# ADJ5V3_3V12V_Sheet_2021-07-20.net
KiCad netlist of a schematic drawn in Altium Designer
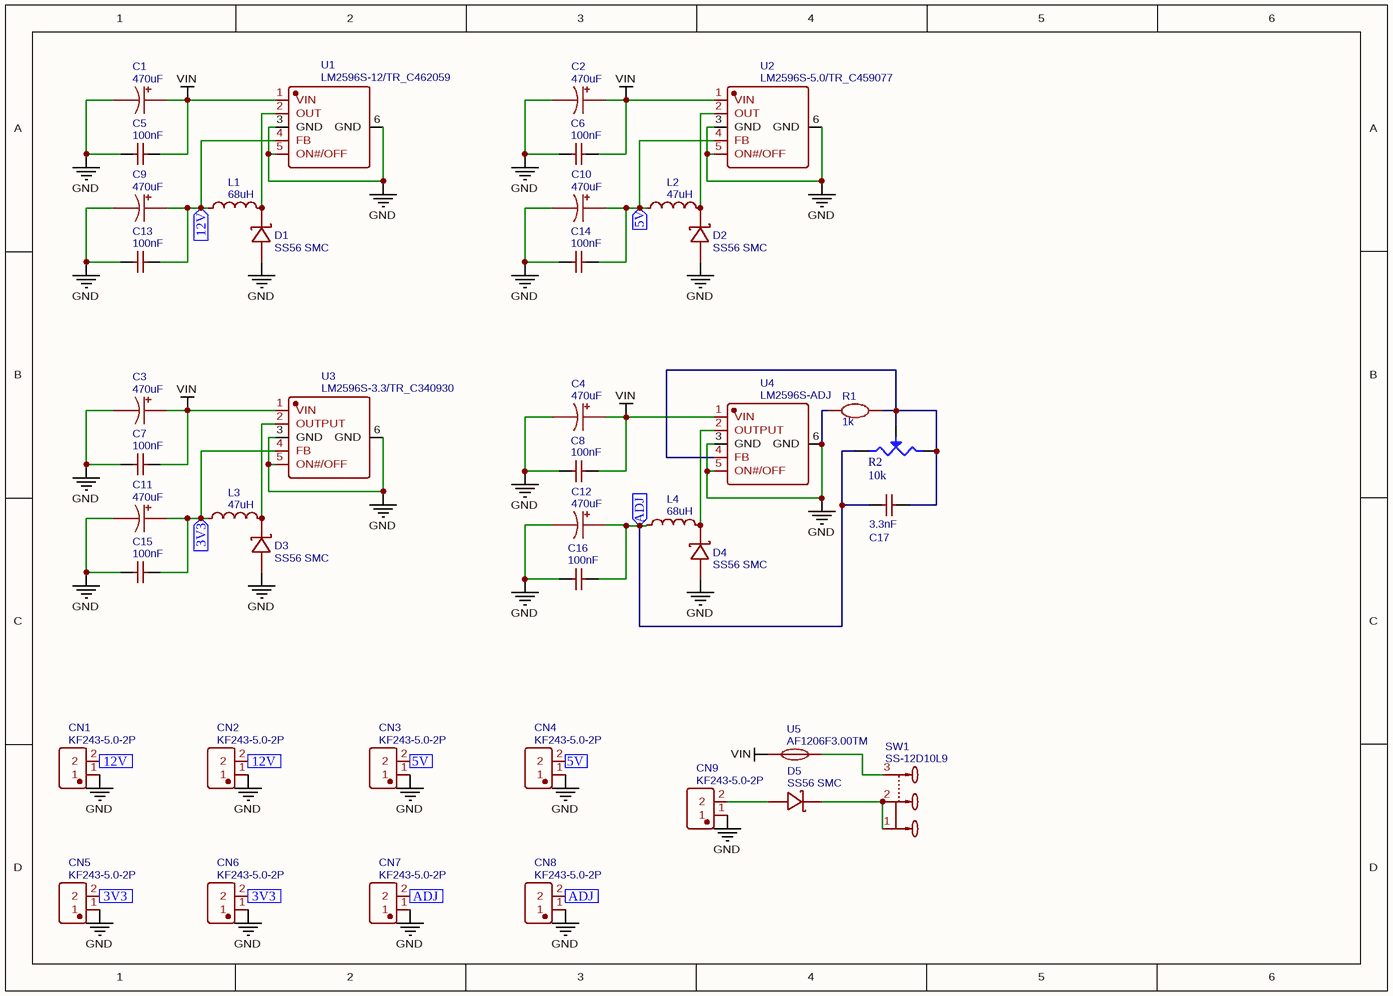
[diagram p0: ADJ5V3.3V12V_Sheet_2021-07-20.schdoc]

(export (version "E")
  (design (tool "Eeschema 10.0.6"))
  (components
    (comp (ref "C1")
      (value "470uF")
      (footprint "CAP-SMD_BD12.5-L13.0-W13.0-FD")
      (fields
        (field (name "BOM_MANUFACTURER PART") "VEJ471M1HTR-1316")
        (field (name "BOM_SUPPLIER PART") "C108926")
        (field (name "CONTRIBUTOR") "LCSC")
      )
      (libsource (lib "altium-import") (part "root_3_470uF_"))
    )
    (comp (ref "C2")
      (value "470uF")
      (footprint "CAP-SMD_BD12.5-L13.0-W13.0-FD")
      (fields
        (field (name "BOM_MANUFACTURER PART") "VEJ471M1HTR-1316")
        (field (name "BOM_SUPPLIER PART") "C108926")
        (field (name "CONTRIBUTOR") "LCSC")
      )
      (libsource (lib "altium-import") (part "root_3_470uF_"))
    )
    (comp (ref "C3")
      (value "470uF")
      (footprint "CAP-SMD_BD12.5-L13.0-W13.0-FD")
      (fields
        (field (name "BOM_MANUFACTURER PART") "VEJ471M1HTR-1316")
        (field (name "BOM_SUPPLIER PART") "C108926")
        (field (name "CONTRIBUTOR") "LCSC")
      )
      (libsource (lib "altium-import") (part "root_3_470uF_"))
    )
    (comp (ref "C4")
      (value "470uF")
      (footprint "CAP-SMD_BD12.5-L13.0-W13.0-FD")
      (fields
        (field (name "BOM_MANUFACTURER PART") "VEJ471M1HTR-1316")
        (field (name "BOM_SUPPLIER PART") "C108926")
        (field (name "CONTRIBUTOR") "LCSC")
      )
      (libsource (lib "altium-import") (part "root_3_470uF_"))
    )
    (comp (ref "C5")
      (value "100nF")
      (footprint "C1210")
      (fields
        (field (name "BOM_MANUFACTURER PART") "C1210X104K251T")
        (field (name "BOM_SUPPLIER PART") "C106103")
      )
      (libsource (lib "altium-import") (part "root_0_100nF_"))
    )
    (comp (ref "C6")
      (value "100nF")
      (footprint "C1210")
      (fields
        (field (name "BOM_MANUFACTURER PART") "C1210X104K251T")
        (field (name "BOM_SUPPLIER PART") "C106103")
      )
      (libsource (lib "altium-import") (part "root_0_100nF_"))
    )
    (comp (ref "C7")
      (value "100nF")
      (footprint "C1210")
      (fields
        (field (name "BOM_MANUFACTURER PART") "C1210X104K251T")
        (field (name "BOM_SUPPLIER PART") "C106103")
      )
      (libsource (lib "altium-import") (part "root_0_100nF_"))
    )
    (comp (ref "C8")
      (value "100nF")
      (footprint "C1210")
      (fields
        (field (name "BOM_MANUFACTURER PART") "C1210X104K251T")
        (field (name "BOM_SUPPLIER PART") "C106103")
      )
      (libsource (lib "altium-import") (part "root_0_100nF_"))
    )
    (comp (ref "C9")
      (value "470uF")
      (footprint "CAP-SMD_BD12.5-L13.0-W13.0-FD")
      (fields
        (field (name "BOM_MANUFACTURER PART") "VEJ471M1HTR-1316")
        (field (name "BOM_SUPPLIER PART") "C108926")
        (field (name "CONTRIBUTOR") "LCSC")
      )
      (libsource (lib "altium-import") (part "root_3_470uF_"))
    )
    (comp (ref "C10")
      (value "470uF")
      (footprint "CAP-SMD_BD12.5-L13.0-W13.0-FD")
      (fields
        (field (name "BOM_MANUFACTURER PART") "VEJ471M1HTR-1316")
        (field (name "BOM_SUPPLIER PART") "C108926")
        (field (name "CONTRIBUTOR") "LCSC")
      )
      (libsource (lib "altium-import") (part "root_3_470uF_"))
    )
    (comp (ref "C11")
      (value "470uF")
      (footprint "CAP-SMD_BD12.5-L13.0-W13.0-FD")
      (fields
        (field (name "BOM_MANUFACTURER PART") "VEJ471M1HTR-1316")
        (field (name "BOM_SUPPLIER PART") "C108926")
        (field (name "CONTRIBUTOR") "LCSC")
      )
      (libsource (lib "altium-import") (part "root_3_470uF_"))
    )
    (comp (ref "C12")
      (value "470uF")
      (footprint "CAP-SMD_BD12.5-L13.0-W13.0-FD")
      (fields
        (field (name "BOM_MANUFACTURER PART") "VEJ471M1HTR-1316")
        (field (name "BOM_SUPPLIER PART") "C108926")
        (field (name "CONTRIBUTOR") "LCSC")
      )
      (libsource (lib "altium-import") (part "root_3_470uF_"))
    )
    (comp (ref "C13")
      (value "100nF")
      (footprint "C1210")
      (fields
        (field (name "BOM_MANUFACTURER PART") "C1210X104K251T")
        (field (name "BOM_SUPPLIER PART") "C106103")
      )
      (libsource (lib "altium-import") (part "root_0_100nF_"))
    )
    (comp (ref "C14")
      (value "100nF")
      (footprint "C1210")
      (fields
        (field (name "BOM_MANUFACTURER PART") "C1210X104K251T")
        (field (name "BOM_SUPPLIER PART") "C106103")
      )
      (libsource (lib "altium-import") (part "root_0_100nF_"))
    )
    (comp (ref "C15")
      (value "100nF")
      (footprint "C1210")
      (fields
        (field (name "BOM_MANUFACTURER PART") "C1210X104K251T")
        (field (name "BOM_SUPPLIER PART") "C106103")
      )
      (libsource (lib "altium-import") (part "root_0_100nF_"))
    )
    (comp (ref "C16")
      (value "100nF")
      (footprint "C1210")
      (fields
        (field (name "BOM_MANUFACTURER PART") "C1210X104K251T")
        (field (name "BOM_SUPPLIER PART") "C106103")
      )
      (libsource (lib "altium-import") (part "root_0_100nF_"))
    )
    (comp (ref "C17")
      (value "3.3nF")
      (footprint "C1210")
      (fields
        (field (name "BOM_MANUFACTURER PART") "C1210X104K251T")
        (field (name "BOM_SUPPLIER PART") "C106103")
      )
      (libsource (lib "altium-import") (part "root_0_100nF_"))
    )
    (comp (ref "CN1")
      (value "KF243-5.0-2P")
      (footprint "CONN-TH_P5.00_KF243-5.0-2P")
      (fields (field (name "BOM_SUPPLIER PART") "C475222") (field (name "CONTRIBUTOR") "LCSC"))
      (libsource (lib "altium-import") (part "root_2_KF243-5.0-2P_"))
    )
    (comp (ref "CN2")
      (value "KF243-5.0-2P")
      (footprint "CONN-TH_P5.00_KF243-5.0-2P")
      (fields (field (name "BOM_SUPPLIER PART") "C475222") (field (name "CONTRIBUTOR") "LCSC"))
      (libsource (lib "altium-import") (part "root_2_KF243-5.0-2P_"))
    )
    (comp (ref "CN3")
      (value "KF243-5.0-2P")
      (footprint "CONN-TH_P5.00_KF243-5.0-2P")
      (fields (field (name "BOM_SUPPLIER PART") "C475222") (field (name "CONTRIBUTOR") "LCSC"))
      (libsource (lib "altium-import") (part "root_2_KF243-5.0-2P_"))
    )
    (comp (ref "CN4")
      (value "KF243-5.0-2P")
      (footprint "CONN-TH_P5.00_KF243-5.0-2P")
      (fields (field (name "BOM_SUPPLIER PART") "C475222") (field (name "CONTRIBUTOR") "LCSC"))
      (libsource (lib "altium-import") (part "root_2_KF243-5.0-2P_"))
    )
    (comp (ref "CN5")
      (value "KF243-5.0-2P")
      (footprint "CONN-TH_P5.00_KF243-5.0-2P")
      (fields (field (name "BOM_SUPPLIER PART") "C475222") (field (name "CONTRIBUTOR") "LCSC"))
      (libsource (lib "altium-import") (part "root_2_KF243-5.0-2P_"))
    )
    (comp (ref "CN6")
      (value "KF243-5.0-2P")
      (footprint "CONN-TH_P5.00_KF243-5.0-2P")
      (fields (field (name "BOM_SUPPLIER PART") "C475222") (field (name "CONTRIBUTOR") "LCSC"))
      (libsource (lib "altium-import") (part "root_2_KF243-5.0-2P_"))
    )
    (comp (ref "CN7")
      (value "KF243-5.0-2P")
      (footprint "CONN-TH_P5.00_KF243-5.0-2P")
      (fields (field (name "BOM_SUPPLIER PART") "C475222") (field (name "CONTRIBUTOR") "LCSC"))
      (libsource (lib "altium-import") (part "root_2_KF243-5.0-2P_"))
    )
    (comp (ref "CN8")
      (value "KF243-5.0-2P")
      (footprint "CONN-TH_P5.00_KF243-5.0-2P")
      (fields (field (name "BOM_SUPPLIER PART") "C475222") (field (name "CONTRIBUTOR") "LCSC"))
      (libsource (lib "altium-import") (part "root_2_KF243-5.0-2P_"))
    )
    (comp (ref "CN9")
      (value "KF243-5.0-2P")
      (footprint "CONN-TH_P5.00_KF243-5.0-2P")
      (fields (field (name "BOM_SUPPLIER PART") "C475222") (field (name "CONTRIBUTOR") "LCSC"))
      (libsource (lib "altium-import") (part "root_2_KF243-5.0-2P_"))
    )
    (comp (ref "D1")
      (value "SS56 SMC")
      (footprint "SMC_L7.1-W6.2-LS8.1-FD")
      (fields (field (name "BOM_SUPPLIER PART") "C24138"))
      (libsource (lib "altium-import") (part "root_1_SS56 SMC_"))
    )
    (comp (ref "D2")
      (value "SS56 SMC")
      (footprint "SMC_L7.1-W6.2-LS8.1-FD")
      (fields (field (name "BOM_SUPPLIER PART") "C24138"))
      (libsource (lib "altium-import") (part "root_1_SS56 SMC_"))
    )
    (comp (ref "D3")
      (value "SS56 SMC")
      (footprint "SMC_L7.1-W6.2-LS8.1-FD")
      (fields (field (name "BOM_SUPPLIER PART") "C24138"))
      (libsource (lib "altium-import") (part "root_1_SS56 SMC_"))
    )
    (comp (ref "D4")
      (value "SS56 SMC")
      (footprint "SMC_L7.1-W6.2-LS8.1-FD")
      (fields (field (name "BOM_SUPPLIER PART") "C24138"))
      (libsource (lib "altium-import") (part "root_1_SS56 SMC_"))
    )
    (comp (ref "D5")
      (value "SS56 SMC")
      (footprint "SMC_L7.1-W6.2-LS8.1-FD")
      (fields (field (name "BOM_SUPPLIER PART") "C24138"))
      (libsource (lib "altium-import") (part "root_0_SS56 SMC_"))
    )
    (comp (ref "L1")
      (value "68uH")
      (footprint "IND-SMD_L11.5-W10.0")
      (fields (field (name "BOM_SUPPLIER PART") "C497902") (field (name "CONTRIBUTOR") "LCSC"))
      (libsource (lib "altium-import") (part "root_0_68uH_"))
    )
    (comp (ref "L2")
      (value "47uH")
      (footprint "IND-SMD_L11.5-W10.0")
      (fields (field (name "BOM_SUPPLIER PART") "C497901") (field (name "CONTRIBUTOR") "LCSC"))
      (libsource (lib "altium-import") (part "root_0_47uH_"))
    )
    (comp (ref "L3")
      (value "47uH")
      (footprint "IND-SMD_L11.5-W10.0")
      (fields (field (name "BOM_SUPPLIER PART") "C497901") (field (name "CONTRIBUTOR") "LCSC"))
      (libsource (lib "altium-import") (part "root_0_47uH_"))
    )
    (comp (ref "L4")
      (value "68uH")
      (footprint "IND-SMD_L11.5-W10.0")
      (fields (field (name "BOM_SUPPLIER PART") "C497902") (field (name "CONTRIBUTOR") "LCSC"))
      (libsource (lib "altium-import") (part "root_0_68uH_"))
    )
    (comp (ref "R1")
      (value "1k")
      (footprint "R0805")
      (fields (field (name "CONTRIBUTOR") "LCEDA_Lib"))
      (libsource (lib "altium-import") (part "root_2_1k_"))
    )
    (comp (ref "R2") (value "10k") (libsource (lib "常用器件") (part "R-GLIDE")))
    (comp (ref "SW1")
      (value "SS-12D10L9")
      (footprint "SW-TH_SS-12D10L9")
      (fields (field (name "BOM_SUPPLIER PART") "C319011") (field (name "CONTRIBUTOR") "LCSC"))
      (libsource (lib "altium-import") (part "root_1_SS-12D10L9_"))
    )
    (comp (ref "U1")
      (value "LM2596S-12/TR_C462059")
      (footprint "TO-263-5_L10.6-W9.6-P1.70-LS15.9-BR")
      (fields
        (field (name "BOM_SUPPLIER PART") "C462059")
        (field (name "BOM_MANUFACTURER PART") "LM2596S-12/TR")
        (field (name "CONTRIBUTOR") "LCSC")
      )
      (libsource (lib "altium-import") (part "root_0_LM2596S-12/TR_C462059_"))
    )
    (comp (ref "U2")
      (value "LM2596S-5.0/TR_C459077")
      (footprint "TO-263-5_L10.6-W9.6-P1.70-LS15.9-BR")
      (fields
        (field (name "BOM_SUPPLIER PART") "C459077")
        (field (name "BOM_MANUFACTURER PART") "LM2596S-5.0/TR")
        (field (name "CONTRIBUTOR") "LCSC")
      )
      (libsource (lib "altium-import") (part "root_0_LM2596S-5.0/TR_C459077_"))
    )
    (comp (ref "U3")
      (value "LM2596S-3.3/TR_C340930")
      (footprint "TO-263-5_L10.6-W9.6-P1.70-LS15.9-BR")
      (fields
        (field (name "BOM_SUPPLIER PART") "C340930")
        (field (name "BOM_MANUFACTURER PART") "LM2596S-3.3/TR")
        (field (name "CONTRIBUTOR") "LCSC")
      )
      (libsource (lib "altium-import") (part "root_0_LM2596S-3.3/TR_C340930_"))
    )
    (comp (ref "U4")
      (value "LM2596S-ADJ")
      (footprint "TO-263-5_L10.6-W9.6-P1.70-LS15.9-BR")
      (fields
        (field (name "BOM_SUPPLIER PART") "C340933")
        (field (name "BOM_MANUFACTURER PART") "LM2596S-ADJ/TR")
        (field (name "CONTRIBUTOR") "LCSC")
      )
      (libsource (lib "altium-import") (part "root_0_LM2596S-ADJ/TR_C340933_"))
    )
    (comp (ref "U5")
      (value "AF1206F3.00TM")
      (footprint "F1206")
      (fields (field (name "BOM_SUPPLIER PART") "C311025") (field (name "CONTRIBUTOR") "LCSC"))
      (libsource (lib "altium-import") (part "root_0_AF1206F3.00TM_"))
    )
  )
  (nets
    (net (code "1") (name "/3V3") (class "Default")
      (node (ref "C11") (pin "1") (pinfunction "1_1") (pintype "passive"))
      (node (ref "C15") (pin "2") (pinfunction "2_2") (pintype "passive"))
      (node (ref "CN5") (pin "2") (pinfunction "2_2") (pintype "passive"))
      (node (ref "CN6") (pin "2") (pinfunction "2_2") (pintype "passive"))
      (node (ref "L3") (pin "1") (pinfunction "1_1") (pintype "passive"))
      (node (ref "U3") (pin "4") (pinfunction "FB_4") (pintype "passive"))
    )
    (net (code "2") (name "/5V") (class "Default")
      (node (ref "C10") (pin "1") (pinfunction "1_1") (pintype "passive"))
      (node (ref "C14") (pin "2") (pinfunction "2_2") (pintype "passive"))
      (node (ref "CN3") (pin "2") (pinfunction "2_2") (pintype "passive"))
      (node (ref "CN4") (pin "2") (pinfunction "2_2") (pintype "passive"))
      (node (ref "L2") (pin "1") (pinfunction "1_1") (pintype "passive"))
      (node (ref "U2") (pin "4") (pinfunction "FB_4") (pintype "passive"))
    )
    (net (code "3") (name "/12V") (class "Default")
      (node (ref "C13") (pin "2") (pinfunction "2_2") (pintype "passive"))
      (node (ref "C9") (pin "1") (pinfunction "1_1") (pintype "passive"))
      (node (ref "CN1") (pin "2") (pinfunction "2_2") (pintype "passive"))
      (node (ref "CN2") (pin "2") (pinfunction "2_2") (pintype "passive"))
      (node (ref "L1") (pin "1") (pinfunction "1_1") (pintype "passive"))
      (node (ref "U1") (pin "4") (pinfunction "FB_4") (pintype "passive"))
    )
    (net (code "4") (name "/ADJ") (class "Default")
      (node (ref "C12") (pin "1") (pinfunction "1_1") (pintype "passive"))
      (node (ref "C16") (pin "2") (pinfunction "2_2") (pintype "passive"))
      (node (ref "C17") (pin "1") (pinfunction "1_1") (pintype "passive"))
      (node (ref "CN7") (pin "2") (pinfunction "2_2") (pintype "passive"))
      (node (ref "CN8") (pin "2") (pinfunction "2_2") (pintype "passive"))
      (node (ref "L4") (pin "1") (pinfunction "1_1") (pintype "passive"))
      (node (ref "R2") (pin "1") (pinfunction "1_1") (pintype "passive"))
    )
    (net (code "5") (name "GND") (class "Default")
      (node (ref "C1") (pin "2") (pinfunction "2_2") (pintype "passive"))
      (node (ref "C10") (pin "2") (pinfunction "2_2") (pintype "passive"))
      (node (ref "C11") (pin "2") (pinfunction "2_2") (pintype "passive"))
      (node (ref "C12") (pin "2") (pinfunction "2_2") (pintype "passive"))
      (node (ref "C13") (pin "1") (pinfunction "1_1") (pintype "passive"))
      (node (ref "C14") (pin "1") (pinfunction "1_1") (pintype "passive"))
      (node (ref "C15") (pin "1") (pinfunction "1_1") (pintype "passive"))
      (node (ref "C16") (pin "1") (pinfunction "1_1") (pintype "passive"))
      (node (ref "C2") (pin "2") (pinfunction "2_2") (pintype "passive"))
      (node (ref "C3") (pin "2") (pinfunction "2_2") (pintype "passive"))
      (node (ref "C4") (pin "2") (pinfunction "2_2") (pintype "passive"))
      (node (ref "C5") (pin "1") (pinfunction "1_1") (pintype "passive"))
      (node (ref "C6") (pin "1") (pinfunction "1_1") (pintype "passive"))
      (node (ref "C7") (pin "1") (pinfunction "1_1") (pintype "passive"))
      (node (ref "C8") (pin "1") (pinfunction "1_1") (pintype "passive"))
      (node (ref "C9") (pin "2") (pinfunction "2_2") (pintype "passive"))
      (node (ref "CN1") (pin "1") (pinfunction "1_1") (pintype "passive"))
      (node (ref "CN2") (pin "1") (pinfunction "1_1") (pintype "passive"))
      (node (ref "CN3") (pin "1") (pinfunction "1_1") (pintype "passive"))
      (node (ref "CN4") (pin "1") (pinfunction "1_1") (pintype "passive"))
      (node (ref "CN5") (pin "1") (pinfunction "1_1") (pintype "passive"))
      (node (ref "CN6") (pin "1") (pinfunction "1_1") (pintype "passive"))
      (node (ref "CN7") (pin "1") (pinfunction "1_1") (pintype "passive"))
      (node (ref "CN8") (pin "1") (pinfunction "1_1") (pintype "passive"))
      (node (ref "CN9") (pin "1") (pinfunction "1_1") (pintype "passive"))
      (node (ref "D1") (pin "1") (pinfunction "A_1") (pintype "passive"))
      (node (ref "D2") (pin "1") (pinfunction "A_1") (pintype "passive"))
      (node (ref "D3") (pin "1") (pinfunction "A_1") (pintype "passive"))
      (node (ref "D4") (pin "1") (pinfunction "A_1") (pintype "passive"))
      (node (ref "R1") (pin "2") (pinfunction "2_2") (pintype "passive"))
      (node (ref "U1") (pin "3") (pinfunction "GND_3") (pintype "passive"))
      (node (ref "U1") (pin "5") (pinfunction "ON#/OFF_5") (pintype "passive"))
      (node (ref "U1") (pin "6") (pinfunction "GND_6") (pintype "passive"))
      (node (ref "U2") (pin "3") (pinfunction "GND_3") (pintype "passive"))
      (node (ref "U2") (pin "5") (pinfunction "ON#/OFF_5") (pintype "passive"))
      (node (ref "U2") (pin "6") (pinfunction "GND_6") (pintype "passive"))
      (node (ref "U3") (pin "3") (pinfunction "GND_3") (pintype "passive"))
      (node (ref "U3") (pin "5") (pinfunction "ON#/OFF_5") (pintype "passive"))
      (node (ref "U3") (pin "6") (pinfunction "GND_6") (pintype "passive"))
      (node (ref "U4") (pin "3") (pinfunction "GND_3") (pintype "passive"))
      (node (ref "U4") (pin "5") (pinfunction "ON#/OFF_5") (pintype "passive"))
      (node (ref "U4") (pin "6") (pinfunction "GND_6") (pintype "passive"))
    )
    (net (code "6") (name "Net-(D1-K)") (class "Default")
      (node (ref "D1") (pin "2") (pinfunction "K_2") (pintype "passive"))
      (node (ref "L1") (pin "2") (pinfunction "2_2") (pintype "passive"))
      (node (ref "U1") (pin "2") (pinfunction "OUT_2") (pintype "passive"))
    )
    (net (code "7") (name "Net-(D2-K)") (class "Default")
      (node (ref "D2") (pin "2") (pinfunction "K_2") (pintype "passive"))
      (node (ref "L2") (pin "2") (pinfunction "2_2") (pintype "passive"))
      (node (ref "U2") (pin "2") (pinfunction "OUT_2") (pintype "passive"))
    )
    (net (code "8") (name "Net-(D3-K)") (class "Default")
      (node (ref "D3") (pin "2") (pinfunction "K_2") (pintype "passive"))
      (node (ref "L3") (pin "2") (pinfunction "2_2") (pintype "passive"))
      (node (ref "U3") (pin "2") (pinfunction "OUTPUT_2") (pintype "passive"))
    )
    (net (code "9") (name "Net-(D4-K)") (class "Default")
      (node (ref "D4") (pin "2") (pinfunction "K_2") (pintype "passive"))
      (node (ref "L4") (pin "2") (pinfunction "2_2") (pintype "passive"))
      (node (ref "U4") (pin "2") (pinfunction "OUTPUT_2") (pintype "passive"))
    )
    (net (code "10") (name "Net-(D5-A)") (class "Default")
      (node (ref "CN9") (pin "2") (pinfunction "2_2") (pintype "passive"))
      (node (ref "D5") (pin "1") (pinfunction "A_1") (pintype "passive"))
    )
    (net (code "11") (name "Net-(D5-K)") (class "Default")
      (node (ref "D5") (pin "2") (pinfunction "K_2") (pintype "passive"))
      (node (ref "SW1") (pin "1") (pinfunction "1_1") (pintype "passive"))
      (node (ref "SW1") (pin "2") (pinfunction "2_2") (pintype "passive"))
    )
    (net (code "12") (name "Net-(R2-W)") (class "Default")
      (node (ref "C17") (pin "2") (pinfunction "2_2") (pintype "passive"))
      (node (ref "R1") (pin "1") (pinfunction "1_1") (pintype "passive"))
      (node (ref "R2") (pin "2") (pinfunction "2_2") (pintype "passive"))
      (node (ref "R2") (pin "3") (pinfunction "W_3") (pintype "passive"))
      (node (ref "U4") (pin "4") (pinfunction "FB_4") (pintype "passive"))
    )
    (net (code "13") (name "Net-(SW1-Pad3)") (class "Default")
      (node (ref "SW1") (pin "3") (pinfunction "3_3") (pintype "passive"))
      (node (ref "U5") (pin "2") (pinfunction "2_2") (pintype "passive"))
    )
    (net (code "14") (name "VIN") (class "Default")
      (node (ref "C1") (pin "1") (pinfunction "1_1") (pintype "passive"))
      (node (ref "C2") (pin "1") (pinfunction "1_1") (pintype "passive"))
      (node (ref "C3") (pin "1") (pinfunction "1_1") (pintype "passive"))
      (node (ref "C4") (pin "1") (pinfunction "1_1") (pintype "passive"))
      (node (ref "C5") (pin "2") (pinfunction "2_2") (pintype "passive"))
      (node (ref "C6") (pin "2") (pinfunction "2_2") (pintype "passive"))
      (node (ref "C7") (pin "2") (pinfunction "2_2") (pintype "passive"))
      (node (ref "C8") (pin "2") (pinfunction "2_2") (pintype "passive"))
      (node (ref "U1") (pin "1") (pinfunction "VIN_1") (pintype "passive"))
      (node (ref "U2") (pin "1") (pinfunction "VIN_1") (pintype "passive"))
      (node (ref "U3") (pin "1") (pinfunction "VIN_1") (pintype "passive"))
      (node (ref "U4") (pin "1") (pinfunction "VIN_1") (pintype "passive"))
      (node (ref "U5") (pin "1") (pinfunction "1_1") (pintype "passive"))
    )
  )
)
